# CapBank_Layout.net
KiCad netlist of a schematic drawn in EAGLE
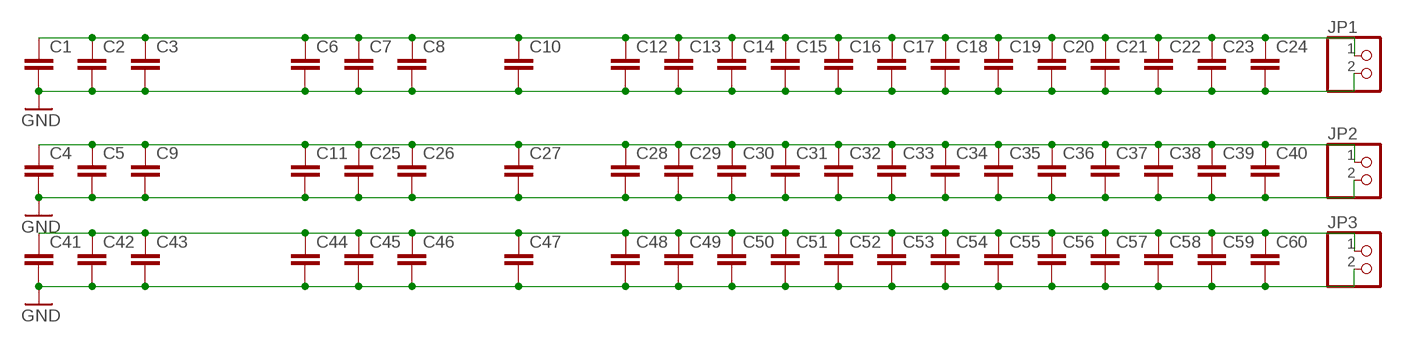
[diagram p0: schematic, sheet 1]

(export (version "E")
  (design (tool "Eeschema 10.0.6"))
  (components
    (comp (ref "C1")
      (value "C5/5")
      (footprint "eagle-import:C5B5")
      (libsource (lib "eagle-import") (part "C5/5"))
    )
    (comp (ref "C2")
      (value "C5/5")
      (footprint "eagle-import:C5B5")
      (libsource (lib "eagle-import") (part "C5/5"))
    )
    (comp (ref "C3")
      (value "C5/5")
      (footprint "eagle-import:C5B5")
      (libsource (lib "eagle-import") (part "C5/5"))
    )
    (comp (ref "C4")
      (value "C5/5")
      (footprint "eagle-import:C5B5")
      (libsource (lib "eagle-import") (part "C5/5"))
    )
    (comp (ref "C5")
      (value "C5/5")
      (footprint "eagle-import:C5B5")
      (libsource (lib "eagle-import") (part "C5/5"))
    )
    (comp (ref "C6")
      (value "C5/5")
      (footprint "eagle-import:C5B5")
      (libsource (lib "eagle-import") (part "C5/5"))
    )
    (comp (ref "C7")
      (value "C5/5")
      (footprint "eagle-import:C5B5")
      (libsource (lib "eagle-import") (part "C5/5"))
    )
    (comp (ref "C8")
      (value "C5/5")
      (footprint "eagle-import:C5B5")
      (libsource (lib "eagle-import") (part "C5/5"))
    )
    (comp (ref "C9")
      (value "C5/5")
      (footprint "eagle-import:C5B5")
      (libsource (lib "eagle-import") (part "C5/5"))
    )
    (comp (ref "C10")
      (value "C5/5")
      (footprint "eagle-import:C5B5")
      (libsource (lib "eagle-import") (part "C5/5"))
    )
    (comp (ref "C11")
      (value "C5/5")
      (footprint "eagle-import:C5B5")
      (libsource (lib "eagle-import") (part "C5/5"))
    )
    (comp (ref "C12")
      (value "C5/5")
      (footprint "eagle-import:C5B5")
      (libsource (lib "eagle-import") (part "C5/5"))
    )
    (comp (ref "C13")
      (value "C5/5")
      (footprint "eagle-import:C5B5")
      (libsource (lib "eagle-import") (part "C5/5"))
    )
    (comp (ref "C14")
      (value "C5/5")
      (footprint "eagle-import:C5B5")
      (libsource (lib "eagle-import") (part "C5/5"))
    )
    (comp (ref "C15")
      (value "C5/5")
      (footprint "eagle-import:C5B5")
      (libsource (lib "eagle-import") (part "C5/5"))
    )
    (comp (ref "C16")
      (value "C5/5")
      (footprint "eagle-import:C5B5")
      (libsource (lib "eagle-import") (part "C5/5"))
    )
    (comp (ref "C17")
      (value "C5/5")
      (footprint "eagle-import:C5B5")
      (libsource (lib "eagle-import") (part "C5/5"))
    )
    (comp (ref "C18")
      (value "C5/5")
      (footprint "eagle-import:C5B5")
      (libsource (lib "eagle-import") (part "C5/5"))
    )
    (comp (ref "C19")
      (value "C5/5")
      (footprint "eagle-import:C5B5")
      (libsource (lib "eagle-import") (part "C5/5"))
    )
    (comp (ref "C20")
      (value "C5/5")
      (footprint "eagle-import:C5B5")
      (libsource (lib "eagle-import") (part "C5/5"))
    )
    (comp (ref "C21")
      (value "C5/5")
      (footprint "eagle-import:C5B5")
      (libsource (lib "eagle-import") (part "C5/5"))
    )
    (comp (ref "C22")
      (value "C5/5")
      (footprint "eagle-import:C5B5")
      (libsource (lib "eagle-import") (part "C5/5"))
    )
    (comp (ref "C23")
      (value "C5/5")
      (footprint "eagle-import:C5B5")
      (libsource (lib "eagle-import") (part "C5/5"))
    )
    (comp (ref "C24")
      (value "C5/5")
      (footprint "eagle-import:C5B5")
      (libsource (lib "eagle-import") (part "C5/5"))
    )
    (comp (ref "C25")
      (value "C5/5")
      (footprint "eagle-import:C5B5")
      (libsource (lib "eagle-import") (part "C5/5"))
    )
    (comp (ref "C26")
      (value "C5/5")
      (footprint "eagle-import:C5B5")
      (libsource (lib "eagle-import") (part "C5/5"))
    )
    (comp (ref "C27")
      (value "C5/5")
      (footprint "eagle-import:C5B5")
      (libsource (lib "eagle-import") (part "C5/5"))
    )
    (comp (ref "C28")
      (value "C5/5")
      (footprint "eagle-import:C5B5")
      (libsource (lib "eagle-import") (part "C5/5"))
    )
    (comp (ref "C29")
      (value "C5/5")
      (footprint "eagle-import:C5B5")
      (libsource (lib "eagle-import") (part "C5/5"))
    )
    (comp (ref "C30")
      (value "C5/5")
      (footprint "eagle-import:C5B5")
      (libsource (lib "eagle-import") (part "C5/5"))
    )
    (comp (ref "C31")
      (value "C5/5")
      (footprint "eagle-import:C5B5")
      (libsource (lib "eagle-import") (part "C5/5"))
    )
    (comp (ref "C32")
      (value "C5/5")
      (footprint "eagle-import:C5B5")
      (libsource (lib "eagle-import") (part "C5/5"))
    )
    (comp (ref "C33")
      (value "C5/5")
      (footprint "eagle-import:C5B5")
      (libsource (lib "eagle-import") (part "C5/5"))
    )
    (comp (ref "C34")
      (value "C5/5")
      (footprint "eagle-import:C5B5")
      (libsource (lib "eagle-import") (part "C5/5"))
    )
    (comp (ref "C35")
      (value "C5/5")
      (footprint "eagle-import:C5B5")
      (libsource (lib "eagle-import") (part "C5/5"))
    )
    (comp (ref "C36")
      (value "C5/5")
      (footprint "eagle-import:C5B5")
      (libsource (lib "eagle-import") (part "C5/5"))
    )
    (comp (ref "C37")
      (value "C5/5")
      (footprint "eagle-import:C5B5")
      (libsource (lib "eagle-import") (part "C5/5"))
    )
    (comp (ref "C38")
      (value "C5/5")
      (footprint "eagle-import:C5B5")
      (libsource (lib "eagle-import") (part "C5/5"))
    )
    (comp (ref "C39")
      (value "C5/5")
      (footprint "eagle-import:C5B5")
      (libsource (lib "eagle-import") (part "C5/5"))
    )
    (comp (ref "C40")
      (value "C5/5")
      (footprint "eagle-import:C5B5")
      (libsource (lib "eagle-import") (part "C5/5"))
    )
    (comp (ref "C41")
      (value "C5/5")
      (footprint "eagle-import:C5B5")
      (libsource (lib "eagle-import") (part "C5/5"))
    )
    (comp (ref "C42")
      (value "C5/5")
      (footprint "eagle-import:C5B5")
      (libsource (lib "eagle-import") (part "C5/5"))
    )
    (comp (ref "C43")
      (value "C5/5")
      (footprint "eagle-import:C5B5")
      (libsource (lib "eagle-import") (part "C5/5"))
    )
    (comp (ref "C44")
      (value "C5/5")
      (footprint "eagle-import:C5B5")
      (libsource (lib "eagle-import") (part "C5/5"))
    )
    (comp (ref "C45")
      (value "C5/5")
      (footprint "eagle-import:C5B5")
      (libsource (lib "eagle-import") (part "C5/5"))
    )
    (comp (ref "C46")
      (value "C5/5")
      (footprint "eagle-import:C5B5")
      (libsource (lib "eagle-import") (part "C5/5"))
    )
    (comp (ref "C47")
      (value "C5/5")
      (footprint "eagle-import:C5B5")
      (libsource (lib "eagle-import") (part "C5/5"))
    )
    (comp (ref "C48")
      (value "C5/5")
      (footprint "eagle-import:C5B5")
      (libsource (lib "eagle-import") (part "C5/5"))
    )
    (comp (ref "C49")
      (value "C5/5")
      (footprint "eagle-import:C5B5")
      (libsource (lib "eagle-import") (part "C5/5"))
    )
    (comp (ref "C50")
      (value "C5/5")
      (footprint "eagle-import:C5B5")
      (libsource (lib "eagle-import") (part "C5/5"))
    )
    (comp (ref "C51")
      (value "C5/5")
      (footprint "eagle-import:C5B5")
      (libsource (lib "eagle-import") (part "C5/5"))
    )
    (comp (ref "C52")
      (value "C5/5")
      (footprint "eagle-import:C5B5")
      (libsource (lib "eagle-import") (part "C5/5"))
    )
    (comp (ref "C53")
      (value "C5/5")
      (footprint "eagle-import:C5B5")
      (libsource (lib "eagle-import") (part "C5/5"))
    )
    (comp (ref "C54")
      (value "C5/5")
      (footprint "eagle-import:C5B5")
      (libsource (lib "eagle-import") (part "C5/5"))
    )
    (comp (ref "C55")
      (value "C5/5")
      (footprint "eagle-import:C5B5")
      (libsource (lib "eagle-import") (part "C5/5"))
    )
    (comp (ref "C56")
      (value "C5/5")
      (footprint "eagle-import:C5B5")
      (libsource (lib "eagle-import") (part "C5/5"))
    )
    (comp (ref "C57")
      (value "C5/5")
      (footprint "eagle-import:C5B5")
      (libsource (lib "eagle-import") (part "C5/5"))
    )
    (comp (ref "C58")
      (value "C5/5")
      (footprint "eagle-import:C5B5")
      (libsource (lib "eagle-import") (part "C5/5"))
    )
    (comp (ref "C59")
      (value "C5/5")
      (footprint "eagle-import:C5B5")
      (libsource (lib "eagle-import") (part "C5/5"))
    )
    (comp (ref "C60")
      (value "C5/5")
      (footprint "eagle-import:C5B5")
      (libsource (lib "eagle-import") (part "C5/5"))
    )
    (comp (ref "JP1")
      (value "PINHD-1X2/90")
      (footprint "eagle-import:1X02_90")
      (libsource (lib "eagle-import") (part "PINHD-1X2/90"))
    )
    (comp (ref "JP2")
      (value "PINHD-1X2/90")
      (footprint "eagle-import:1X02_90")
      (libsource (lib "eagle-import") (part "PINHD-1X2/90"))
    )
    (comp (ref "JP3")
      (value "PINHD-1X2/90")
      (footprint "eagle-import:1X02_90")
      (libsource (lib "eagle-import") (part "PINHD-1X2/90"))
    )
  )
  (nets
    (net (code "1") (name "GND") (class "Default")
      (node (ref "C1") (pin "2") (pinfunction "2_2") (pintype "passive"))
      (node (ref "C10") (pin "2") (pinfunction "2_2") (pintype "passive"))
      (node (ref "C11") (pin "2") (pinfunction "2_2") (pintype "passive"))
      (node (ref "C12") (pin "2") (pinfunction "2_2") (pintype "passive"))
      (node (ref "C13") (pin "2") (pinfunction "2_2") (pintype "passive"))
      (node (ref "C14") (pin "2") (pinfunction "2_2") (pintype "passive"))
      (node (ref "C15") (pin "2") (pinfunction "2_2") (pintype "passive"))
      (node (ref "C16") (pin "2") (pinfunction "2_2") (pintype "passive"))
      (node (ref "C17") (pin "2") (pinfunction "2_2") (pintype "passive"))
      (node (ref "C18") (pin "2") (pinfunction "2_2") (pintype "passive"))
      (node (ref "C19") (pin "2") (pinfunction "2_2") (pintype "passive"))
      (node (ref "C2") (pin "2") (pinfunction "2_2") (pintype "passive"))
      (node (ref "C20") (pin "2") (pinfunction "2_2") (pintype "passive"))
      (node (ref "C21") (pin "2") (pinfunction "2_2") (pintype "passive"))
      (node (ref "C22") (pin "2") (pinfunction "2_2") (pintype "passive"))
      (node (ref "C23") (pin "2") (pinfunction "2_2") (pintype "passive"))
      (node (ref "C24") (pin "2") (pinfunction "2_2") (pintype "passive"))
      (node (ref "C25") (pin "2") (pinfunction "2_2") (pintype "passive"))
      (node (ref "C26") (pin "2") (pinfunction "2_2") (pintype "passive"))
      (node (ref "C27") (pin "2") (pinfunction "2_2") (pintype "passive"))
      (node (ref "C28") (pin "2") (pinfunction "2_2") (pintype "passive"))
      (node (ref "C29") (pin "2") (pinfunction "2_2") (pintype "passive"))
      (node (ref "C3") (pin "2") (pinfunction "2_2") (pintype "passive"))
      (node (ref "C30") (pin "2") (pinfunction "2_2") (pintype "passive"))
      (node (ref "C31") (pin "2") (pinfunction "2_2") (pintype "passive"))
      (node (ref "C32") (pin "2") (pinfunction "2_2") (pintype "passive"))
      (node (ref "C33") (pin "2") (pinfunction "2_2") (pintype "passive"))
      (node (ref "C34") (pin "2") (pinfunction "2_2") (pintype "passive"))
      (node (ref "C35") (pin "2") (pinfunction "2_2") (pintype "passive"))
      (node (ref "C36") (pin "2") (pinfunction "2_2") (pintype "passive"))
      (node (ref "C37") (pin "2") (pinfunction "2_2") (pintype "passive"))
      (node (ref "C38") (pin "2") (pinfunction "2_2") (pintype "passive"))
      (node (ref "C39") (pin "2") (pinfunction "2_2") (pintype "passive"))
      (node (ref "C4") (pin "2") (pinfunction "2_2") (pintype "passive"))
      (node (ref "C40") (pin "2") (pinfunction "2_2") (pintype "passive"))
      (node (ref "C41") (pin "2") (pinfunction "2_2") (pintype "passive"))
      (node (ref "C42") (pin "2") (pinfunction "2_2") (pintype "passive"))
      (node (ref "C43") (pin "2") (pinfunction "2_2") (pintype "passive"))
      (node (ref "C44") (pin "2") (pinfunction "2_2") (pintype "passive"))
      (node (ref "C45") (pin "2") (pinfunction "2_2") (pintype "passive"))
      (node (ref "C46") (pin "2") (pinfunction "2_2") (pintype "passive"))
      (node (ref "C47") (pin "2") (pinfunction "2_2") (pintype "passive"))
      (node (ref "C48") (pin "2") (pinfunction "2_2") (pintype "passive"))
      (node (ref "C49") (pin "2") (pinfunction "2_2") (pintype "passive"))
      (node (ref "C5") (pin "2") (pinfunction "2_2") (pintype "passive"))
      (node (ref "C50") (pin "2") (pinfunction "2_2") (pintype "passive"))
      (node (ref "C51") (pin "2") (pinfunction "2_2") (pintype "passive"))
      (node (ref "C52") (pin "2") (pinfunction "2_2") (pintype "passive"))
      (node (ref "C53") (pin "2") (pinfunction "2_2") (pintype "passive"))
      (node (ref "C54") (pin "2") (pinfunction "2_2") (pintype "passive"))
      (node (ref "C55") (pin "2") (pinfunction "2_2") (pintype "passive"))
      (node (ref "C56") (pin "2") (pinfunction "2_2") (pintype "passive"))
      (node (ref "C57") (pin "2") (pinfunction "2_2") (pintype "passive"))
      (node (ref "C58") (pin "2") (pinfunction "2_2") (pintype "passive"))
      (node (ref "C59") (pin "2") (pinfunction "2_2") (pintype "passive"))
      (node (ref "C6") (pin "2") (pinfunction "2_2") (pintype "passive"))
      (node (ref "C60") (pin "2") (pinfunction "2_2") (pintype "passive"))
      (node (ref "C7") (pin "2") (pinfunction "2_2") (pintype "passive"))
      (node (ref "C8") (pin "2") (pinfunction "2_2") (pintype "passive"))
      (node (ref "C9") (pin "2") (pinfunction "2_2") (pintype "passive"))
      (node (ref "JP1") (pin "2") (pinfunction "2_2") (pintype "passive"))
      (node (ref "JP2") (pin "2") (pinfunction "2_2") (pintype "passive"))
      (node (ref "JP3") (pin "2") (pinfunction "2_2") (pintype "passive"))
    )
    (net (code "2") (name "Net-(C1-Pad1)") (class "Default")
      (node (ref "C1") (pin "1") (pinfunction "1_1") (pintype "passive"))
      (node (ref "C10") (pin "1") (pinfunction "1_1") (pintype "passive"))
      (node (ref "C12") (pin "1") (pinfunction "1_1") (pintype "passive"))
      (node (ref "C13") (pin "1") (pinfunction "1_1") (pintype "passive"))
      (node (ref "C14") (pin "1") (pinfunction "1_1") (pintype "passive"))
      (node (ref "C15") (pin "1") (pinfunction "1_1") (pintype "passive"))
      (node (ref "C16") (pin "1") (pinfunction "1_1") (pintype "passive"))
      (node (ref "C17") (pin "1") (pinfunction "1_1") (pintype "passive"))
      (node (ref "C18") (pin "1") (pinfunction "1_1") (pintype "passive"))
      (node (ref "C19") (pin "1") (pinfunction "1_1") (pintype "passive"))
      (node (ref "C2") (pin "1") (pinfunction "1_1") (pintype "passive"))
      (node (ref "C20") (pin "1") (pinfunction "1_1") (pintype "passive"))
      (node (ref "C21") (pin "1") (pinfunction "1_1") (pintype "passive"))
      (node (ref "C22") (pin "1") (pinfunction "1_1") (pintype "passive"))
      (node (ref "C23") (pin "1") (pinfunction "1_1") (pintype "passive"))
      (node (ref "C24") (pin "1") (pinfunction "1_1") (pintype "passive"))
      (node (ref "C3") (pin "1") (pinfunction "1_1") (pintype "passive"))
      (node (ref "C6") (pin "1") (pinfunction "1_1") (pintype "passive"))
      (node (ref "C7") (pin "1") (pinfunction "1_1") (pintype "passive"))
      (node (ref "C8") (pin "1") (pinfunction "1_1") (pintype "passive"))
      (node (ref "JP1") (pin "1") (pinfunction "1_1") (pintype "passive"))
    )
    (net (code "3") (name "Net-(C11-Pad1)") (class "Default")
      (node (ref "C11") (pin "1") (pinfunction "1_1") (pintype "passive"))
      (node (ref "C25") (pin "1") (pinfunction "1_1") (pintype "passive"))
      (node (ref "C26") (pin "1") (pinfunction "1_1") (pintype "passive"))
      (node (ref "C27") (pin "1") (pinfunction "1_1") (pintype "passive"))
      (node (ref "C28") (pin "1") (pinfunction "1_1") (pintype "passive"))
      (node (ref "C29") (pin "1") (pinfunction "1_1") (pintype "passive"))
      (node (ref "C30") (pin "1") (pinfunction "1_1") (pintype "passive"))
      (node (ref "C31") (pin "1") (pinfunction "1_1") (pintype "passive"))
      (node (ref "C32") (pin "1") (pinfunction "1_1") (pintype "passive"))
      (node (ref "C33") (pin "1") (pinfunction "1_1") (pintype "passive"))
      (node (ref "C34") (pin "1") (pinfunction "1_1") (pintype "passive"))
      (node (ref "C35") (pin "1") (pinfunction "1_1") (pintype "passive"))
      (node (ref "C36") (pin "1") (pinfunction "1_1") (pintype "passive"))
      (node (ref "C37") (pin "1") (pinfunction "1_1") (pintype "passive"))
      (node (ref "C38") (pin "1") (pinfunction "1_1") (pintype "passive"))
      (node (ref "C39") (pin "1") (pinfunction "1_1") (pintype "passive"))
      (node (ref "C4") (pin "1") (pinfunction "1_1") (pintype "passive"))
      (node (ref "C40") (pin "1") (pinfunction "1_1") (pintype "passive"))
      (node (ref "C5") (pin "1") (pinfunction "1_1") (pintype "passive"))
      (node (ref "C9") (pin "1") (pinfunction "1_1") (pintype "passive"))
      (node (ref "JP2") (pin "1") (pinfunction "1_1") (pintype "passive"))
    )
    (net (code "4") (name "Net-(C41-Pad1)") (class "Default")
      (node (ref "C41") (pin "1") (pinfunction "1_1") (pintype "passive"))
      (node (ref "C42") (pin "1") (pinfunction "1_1") (pintype "passive"))
      (node (ref "C43") (pin "1") (pinfunction "1_1") (pintype "passive"))
      (node (ref "C44") (pin "1") (pinfunction "1_1") (pintype "passive"))
      (node (ref "C45") (pin "1") (pinfunction "1_1") (pintype "passive"))
      (node (ref "C46") (pin "1") (pinfunction "1_1") (pintype "passive"))
      (node (ref "C47") (pin "1") (pinfunction "1_1") (pintype "passive"))
      (node (ref "C48") (pin "1") (pinfunction "1_1") (pintype "passive"))
      (node (ref "C49") (pin "1") (pinfunction "1_1") (pintype "passive"))
      (node (ref "C50") (pin "1") (pinfunction "1_1") (pintype "passive"))
      (node (ref "C51") (pin "1") (pinfunction "1_1") (pintype "passive"))
      (node (ref "C52") (pin "1") (pinfunction "1_1") (pintype "passive"))
      (node (ref "C53") (pin "1") (pinfunction "1_1") (pintype "passive"))
      (node (ref "C54") (pin "1") (pinfunction "1_1") (pintype "passive"))
      (node (ref "C55") (pin "1") (pinfunction "1_1") (pintype "passive"))
      (node (ref "C56") (pin "1") (pinfunction "1_1") (pintype "passive"))
      (node (ref "C57") (pin "1") (pinfunction "1_1") (pintype "passive"))
      (node (ref "C58") (pin "1") (pinfunction "1_1") (pintype "passive"))
      (node (ref "C59") (pin "1") (pinfunction "1_1") (pintype "passive"))
      (node (ref "C60") (pin "1") (pinfunction "1_1") (pintype "passive"))
      (node (ref "JP3") (pin "1") (pinfunction "1_1") (pintype "passive"))
    )
  )
)
